# BusSelect.net
KiCad netlist of a schematic drawn in Altium Designer
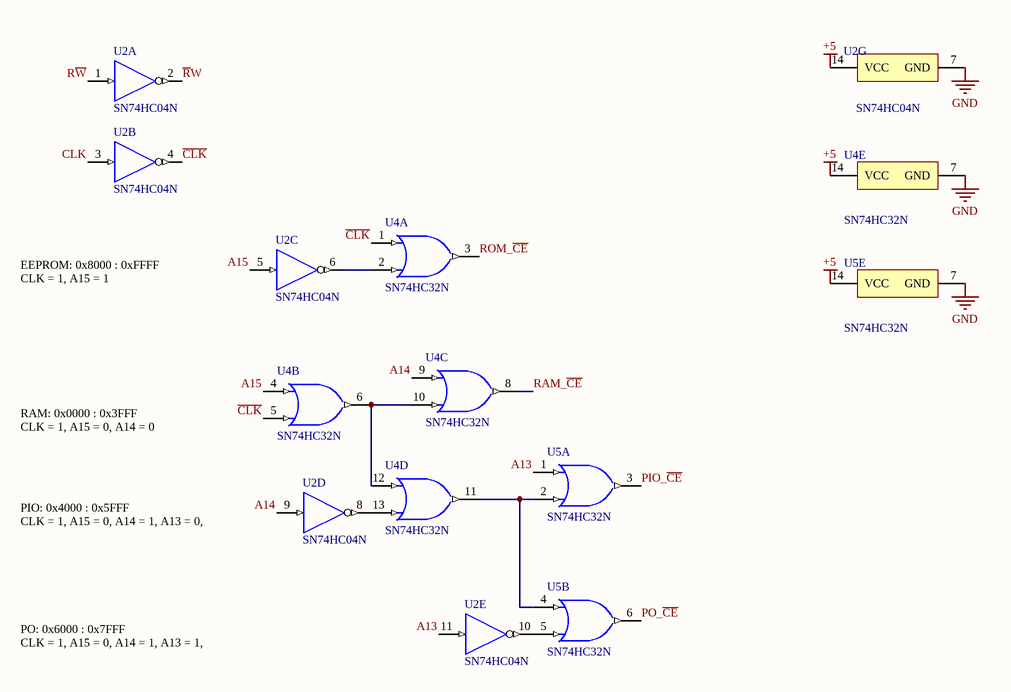
[diagram p0: BusSelect.SchDoc]

(export (version "E")
  (design (tool "Eeschema 10.0.6"))
  (components
    (comp (ref "U2")
      (value "SN74HC04N")
      (footprint "N0014A")
      (description "Hex Inverters, N0014A, TUBE")
      (fields
        (field (name "MANUFACTURER") "Texas Instruments")
        (field (name "GENERIC PART NUMBER") "SN74HC04")
      )
      (libsource (lib "Altium Content Vault") (part "TI-CD_SNX4XXXXXX4X_19A-14"))
    )
    (comp (ref "U4")
      (value "SN74HC32N")
      (footprint "N0014A")
      (description "Quadruple 2-Input Positive-OR Gates, N0014A, TUBE")
      (fields
        (field (name "MANUFACTURER") "Texas Instruments")
        (field (name "GENERIC PART NUMBER") "SN74HC32")
      )
      (libsource (lib "Altium Content Vault") (part "TI-OR-4-2IN-14"))
    )
    (comp (ref "U5")
      (value "SN74HC32N")
      (footprint "N0014A")
      (description "Quadruple 2-Input Positive-OR Gates, N0014A, TUBE")
      (fields
        (field (name "MANUFACTURER") "Texas Instruments")
        (field (name "GENERIC PART NUMBER") "SN74HC32")
      )
      (libsource (lib "Altium Content Vault") (part "TI-OR-4-2IN-14"))
    )
  )
  (nets
    (net (code "1") (name "+5") (class "Default")
      (node (ref "U2") (pin "14") (pinfunction "VCC_14") (pintype "power_in"))
      (node (ref "U4") (pin "14") (pinfunction "VCC_14") (pintype "power_in"))
      (node (ref "U5") (pin "14") (pinfunction "VCC_14") (pintype "power_in"))
    )
    (net (code "2") (name "/A13") (class "Default")
      (node (ref "U2") (pin "11") (pinfunction "5A_11") (pintype "input"))
      (node (ref "U5") (pin "1") (pinfunction "1A_1") (pintype "input"))
    )
    (net (code "3") (name "/A14") (class "Default")
      (node (ref "U2") (pin "9") (pinfunction "4A_9") (pintype "input"))
      (node (ref "U4") (pin "9") (pinfunction "3A_9") (pintype "input"))
    )
    (net (code "4") (name "/A15") (class "Default")
      (node (ref "U2") (pin "5") (pinfunction "3A_5") (pintype "input"))
      (node (ref "U4") (pin "4") (pinfunction "2A_4") (pintype "input"))
    )
    (net (code "5") (name "/CLK") (class "Default")
      (node (ref "U2") (pin "3") (pinfunction "2A_3") (pintype "input"))
    )
    (net (code "6") (name "/PIO_~{CE}") (class "Default")
      (node (ref "U5") (pin "3") (pinfunction "1Y_3") (pintype "output"))
    )
    (net (code "7") (name "/PO_~{CE}") (class "Default")
      (node (ref "U5") (pin "6") (pinfunction "2Y_6") (pintype "output"))
    )
    (net (code "8") (name "/RAM_~{CE}") (class "Default")
      (node (ref "U4") (pin "8") (pinfunction "3Y_8") (pintype "output"))
    )
    (net (code "9") (name "/ROM_~{CE}") (class "Default")
      (node (ref "U4") (pin "3") (pinfunction "1Y_3") (pintype "output"))
    )
    (net (code "10") (name "/R~{W}") (class "Default")
      (node (ref "U2") (pin "1") (pinfunction "1A_1") (pintype "input"))
    )
    (net (code "11") (name "/~{CLK}") (class "Default")
      (node (ref "U2") (pin "4") (pinfunction "~{2Y}_4") (pintype "output"))
      (node (ref "U4") (pin "1") (pinfunction "1A_1") (pintype "input"))
      (node (ref "U4") (pin "5") (pinfunction "2B_5") (pintype "input"))
    )
    (net (code "12") (name "/~{R}W") (class "Default")
      (node (ref "U2") (pin "2") (pinfunction "~{1Y}_2") (pintype "output"))
    )
    (net (code "13") (name "GND") (class "Default")
      (node (ref "U2") (pin "7") (pinfunction "GND_7") (pintype "power_in"))
      (node (ref "U4") (pin "7") (pinfunction "GND_7") (pintype "power_in"))
      (node (ref "U5") (pin "7") (pinfunction "GND_7") (pintype "power_in"))
    )
    (net (code "14") (name "Net-(U2C-~{3Y})") (class "Default")
      (node (ref "U2") (pin "6") (pinfunction "~{3Y}_6") (pintype "output"))
      (node (ref "U4") (pin "2") (pinfunction "1B_2") (pintype "input"))
    )
    (net (code "15") (name "Net-(U2D-~{4Y})") (class "Default")
      (node (ref "U2") (pin "8") (pinfunction "~{4Y}_8") (pintype "output"))
      (node (ref "U4") (pin "13") (pinfunction "4B_13") (pintype "input"))
    )
    (net (code "16") (name "Net-(U2E-~{5Y})") (class "Default")
      (node (ref "U2") (pin "10") (pinfunction "~{5Y}_10") (pintype "output"))
      (node (ref "U5") (pin "5") (pinfunction "2B_5") (pintype "input"))
    )
    (net (code "17") (name "Net-(U4B-2Y)") (class "Default")
      (node (ref "U4") (pin "10") (pinfunction "3B_10") (pintype "input"))
      (node (ref "U4") (pin "12") (pinfunction "4A_12") (pintype "input"))
      (node (ref "U4") (pin "6") (pinfunction "2Y_6") (pintype "output"))
    )
    (net (code "18") (name "Net-(U4D-4Y)") (class "Default")
      (node (ref "U4") (pin "11") (pinfunction "4Y_11") (pintype "output"))
      (node (ref "U5") (pin "2") (pinfunction "1B_2") (pintype "input"))
      (node (ref "U5") (pin "4") (pinfunction "2A_4") (pintype "input"))
    )
  )
)
